# rf_transmitter.net
KiCad netlist of a schematic drawn in Altium Designer
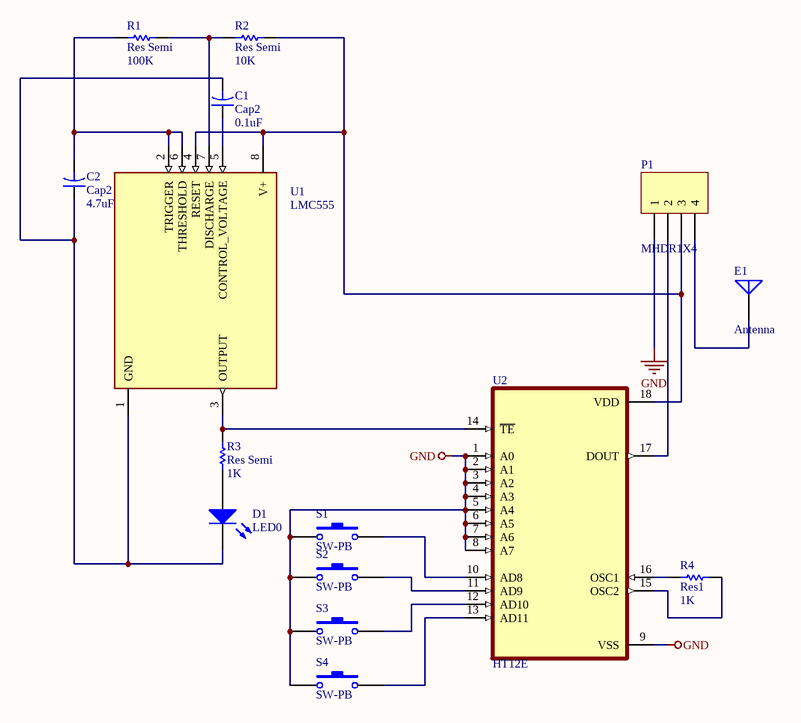
[diagram p0: rf transmitter.SchDoc]

(export (version "E")
  (design (tool "Eeschema 10.0.6"))
  (components
    (comp (ref "C1")
      (value "Cap2")
      (footprint "CAPR5-4X5")
      (description "Capacitor")
      (fields (field (name "ALTIUM_VALUE") "0.1uF") (field (name "PUBLISHER") "Altium Limited"))
      (libsource (lib "Miscellaneous Devices") (part "Cap2"))
    )
    (comp (ref "C2")
      (value "Cap2")
      (footprint "CAPR5-4X5")
      (description "Capacitor")
      (fields (field (name "ALTIUM_VALUE") "4.7uF") (field (name "PUBLISHER") "Altium Limited"))
      (libsource (lib "Miscellaneous Devices") (part "Cap2"))
    )
    (comp (ref "D1")
      (value "LED0")
      (footprint "LED-0")
      (description "Typical INFRARED GaAs LED")
      (fields (field (name "PUBLISHER") "Altium Limited"))
      (libsource (lib "Miscellaneous Devices") (part "LED0"))
    )
    (comp (ref "E1")
      (value "Antenna")
      (footprint "PIN1")
      (description "Generic Antenna")
      (fields (field (name "PUBLISHER") "Altium Limited"))
      (libsource (lib "Miscellaneous Devices") (part "Antenna"))
    )
    (comp (ref "P1")
      (value "MHDR1X4")
      (footprint "MHDR1X4")
      (description "Header, 4-Pin")
      (fields (field (name "PUBLISHER") "Altium Limited"))
      (libsource (lib "Miscellaneous Connectors") (part "MHDR1X4"))
    )
    (comp (ref "R1")
      (value "Res Semi")
      (footprint "AXIAL-0.5")
      (description "Semiconductor Resistor")
      (fields (field (name "ALTIUM_VALUE") "100K") (field (name "PUBLISHER") "Altium Limited"))
      (libsource (lib "Miscellaneous Devices") (part "Res Semi"))
    )
    (comp (ref "R2")
      (value "Res Semi")
      (footprint "AXIAL-0.5")
      (description "Semiconductor Resistor")
      (fields (field (name "ALTIUM_VALUE") "10K") (field (name "PUBLISHER") "Altium Limited"))
      (libsource (lib "Miscellaneous Devices") (part "Res Semi"))
    )
    (comp (ref "R3")
      (value "Res Semi")
      (footprint "AXIAL-0.5")
      (description "Semiconductor Resistor")
      (fields (field (name "ALTIUM_VALUE") "1K") (field (name "PUBLISHER") "Altium Limited"))
      (libsource (lib "Miscellaneous Devices") (part "Res Semi"))
    )
    (comp (ref "R4")
      (value "Res1")
      (footprint "AXIAL-0.3")
      (description "Resistor")
      (fields (field (name "ALTIUM_VALUE") "1K") (field (name "PUBLISHER") "Altium Limited"))
      (libsource (lib "Miscellaneous Devices") (part "Res1"))
    )
    (comp (ref "S1")
      (value "SW-PB")
      (footprint "SPST-2")
      (description "Switch")
      (fields (field (name "PUBLISHER") "Altium Limited"))
      (libsource (lib "Miscellaneous Devices") (part "SW-PB"))
    )
    (comp (ref "S2")
      (value "SW-PB")
      (footprint "SPST-2")
      (description "Switch")
      (fields (field (name "PUBLISHER") "Altium Limited"))
      (libsource (lib "Miscellaneous Devices") (part "SW-PB"))
    )
    (comp (ref "S3")
      (value "SW-PB")
      (footprint "SPST-2")
      (description "Switch")
      (fields (field (name "PUBLISHER") "Altium Limited"))
      (libsource (lib "Miscellaneous Devices") (part "SW-PB"))
    )
    (comp (ref "S4")
      (value "SW-PB")
      (footprint "SPST-2")
      (description "Switch")
      (fields (field (name "PUBLISHER") "Altium Limited"))
      (libsource (lib "Miscellaneous Devices") (part "SW-PB"))
    )
    (comp (ref "U1") (value "LMC555") (footprint "LMC555new") (libsource (lib "Schlib1") (part "LMC555")))
    (comp (ref "U2") (value "HT12E") (footprint "HT12E") (libsource (lib "Schlib1") (part "Encoder")))
  )
  (nets
    (net (code "1") (name "GND") (class "Default")
      (node (ref "P1") (pin "1") (pinfunction "1_1") (pintype "passive"))
      (node (ref "S1") (pin "1") (pinfunction "1_1") (pintype "passive"))
      (node (ref "S2") (pin "1") (pinfunction "1_1") (pintype "passive"))
      (node (ref "S3") (pin "1") (pinfunction "1_1") (pintype "passive"))
      (node (ref "S4") (pin "1") (pinfunction "1_1") (pintype "passive"))
      (node (ref "U2") (pin "1") (pinfunction "A0_1") (pintype "input"))
      (node (ref "U2") (pin "2") (pinfunction "A1_2") (pintype "input"))
      (node (ref "U2") (pin "3") (pinfunction "A2_3") (pintype "input"))
      (node (ref "U2") (pin "4") (pinfunction "A3_4") (pintype "input"))
      (node (ref "U2") (pin "5") (pinfunction "A4_5") (pintype "input"))
      (node (ref "U2") (pin "6") (pinfunction "A5_6") (pintype "input"))
      (node (ref "U2") (pin "7") (pinfunction "A6_7") (pintype "input"))
      (node (ref "U2") (pin "8") (pinfunction "A7_8") (pintype "input"))
      (node (ref "U2") (pin "9") (pinfunction "VSS_9") (pintype "power_in"))
    )
    (net (code "2") (name "Net-(D1-A)") (class "Default")
      (node (ref "D1") (pin "1") (pinfunction "A_1") (pintype "passive"))
      (node (ref "R3") (pin "1") (pinfunction "1_1") (pintype "passive"))
    )
    (net (code "3") (name "Net-(D1-K)") (class "Default")
      (node (ref "C1") (pin "2") (pinfunction "2_2") (pintype "passive"))
      (node (ref "C2") (pin "1") (pinfunction "1_1") (pintype "passive"))
      (node (ref "D1") (pin "2") (pinfunction "K_2") (pintype "passive"))
      (node (ref "U1") (pin "1") (pinfunction "GND_1") (pintype "power_in"))
    )
    (net (code "4") (name "Net-(E1-A)") (class "Default")
      (node (ref "E1") (pin "1") (pinfunction "A_1") (pintype "passive"))
      (node (ref "P1") (pin "4") (pinfunction "4_4") (pintype "passive"))
    )
    (net (code "5") (name "Net-(U1-CONTROL_VOLTAGE)") (class "Default")
      (node (ref "C1") (pin "1") (pinfunction "1_1") (pintype "passive"))
      (node (ref "U1") (pin "5") (pinfunction "CONTROL_VOLTAGE_5") (pintype "input"))
    )
    (net (code "6") (name "Net-(U1-DISCHARGE)") (class "Default")
      (node (ref "R1") (pin "2") (pinfunction "2_2") (pintype "passive"))
      (node (ref "R2") (pin "1") (pinfunction "1_1") (pintype "passive"))
      (node (ref "U1") (pin "7") (pinfunction "DISCHARGE_7") (pintype "input"))
    )
    (net (code "7") (name "Net-(U1-OUTPUT)") (class "Default")
      (node (ref "R3") (pin "2") (pinfunction "2_2") (pintype "passive"))
      (node (ref "U1") (pin "3") (pinfunction "OUTPUT_3") (pintype "output"))
      (node (ref "U2") (pin "14") (pinfunction "~{TE}_14") (pintype "input"))
    )
    (net (code "8") (name "Net-(U1-RESET)") (class "Default")
      (node (ref "P1") (pin "3") (pinfunction "3_3") (pintype "passive"))
      (node (ref "R2") (pin "2") (pinfunction "2_2") (pintype "passive"))
      (node (ref "U1") (pin "4") (pinfunction "RESET_4") (pintype "input"))
      (node (ref "U1") (pin "8") (pinfunction "V+_8") (pintype "power_in"))
      (node (ref "U2") (pin "18") (pinfunction "VDD_18") (pintype "power_in"))
    )
    (net (code "9") (name "Net-(U1-THRESHOLD)") (class "Default")
      (node (ref "C2") (pin "2") (pinfunction "2_2") (pintype "passive"))
      (node (ref "R1") (pin "1") (pinfunction "1_1") (pintype "passive"))
      (node (ref "U1") (pin "2") (pinfunction "TRIGGER_2") (pintype "input"))
      (node (ref "U1") (pin "6") (pinfunction "THRESHOLD_6") (pintype "input"))
    )
    (net (code "10") (name "Net-(U2-AD8)") (class "Default")
      (node (ref "S1") (pin "2") (pinfunction "2_2") (pintype "passive"))
      (node (ref "U2") (pin "10") (pinfunction "AD8_10") (pintype "input"))
    )
    (net (code "11") (name "Net-(U2-AD9)") (class "Default")
      (node (ref "S2") (pin "2") (pinfunction "2_2") (pintype "passive"))
      (node (ref "U2") (pin "11") (pinfunction "AD9_11") (pintype "input"))
    )
    (net (code "12") (name "Net-(U2-AD10)") (class "Default")
      (node (ref "S3") (pin "2") (pinfunction "2_2") (pintype "passive"))
      (node (ref "U2") (pin "12") (pinfunction "AD10_12") (pintype "input"))
    )
    (net (code "13") (name "Net-(U2-AD11)") (class "Default")
      (node (ref "S4") (pin "2") (pinfunction "2_2") (pintype "passive"))
      (node (ref "U2") (pin "13") (pinfunction "AD11_13") (pintype "input"))
    )
    (net (code "14") (name "Net-(U2-DOUT)") (class "Default")
      (node (ref "P1") (pin "2") (pinfunction "2_2") (pintype "passive"))
      (node (ref "U2") (pin "17") (pinfunction "DOUT_17") (pintype "output"))
    )
    (net (code "15") (name "Net-(U2-OSC1)") (class "Default")
      (node (ref "R4") (pin "1") (pinfunction "1_1") (pintype "passive"))
      (node (ref "U2") (pin "16") (pinfunction "OSC1_16") (pintype "input"))
    )
    (net (code "16") (name "Net-(U2-OSC2)") (class "Default")
      (node (ref "R4") (pin "2") (pinfunction "2_2") (pintype "passive"))
      (node (ref "U2") (pin "15") (pinfunction "OSC2_15") (pintype "output"))
    )
  )
)
